# Buzzer.net
KiCad netlist of a schematic drawn in Altium Designer
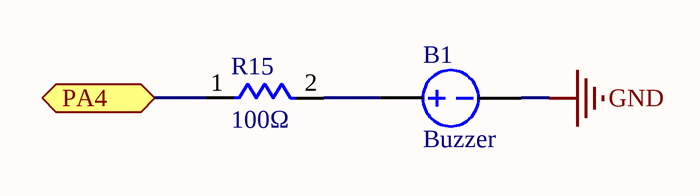
[diagram p0: Buzzer.SchDoc]

(export (version "E")
  (design (tool "Eeschema 10.0.6"))
  (components
    (comp (ref "B1")
      (value "Buzzer")
      (footprint "Buzzer")
      (libsource (lib "Faydali_Yuk_Schlib1") (part "Buzzer"))
    )
    (comp (ref "R15")
      (value "100Ω")
      (footprint "RES - 0603")
      (description "SMD Res")
      (libsource (lib "Faydali_Yuk_Schlib1") (part "Res"))
    )
  )
  (nets
    (net (code "1") (name "/PA4") (class "Default")
      (node (ref "R15") (pin "1") (pinfunction "1_1") (pintype "passive"))
    )
    (net (code "2") (name "GND") (class "Default")
      (node (ref "B1") (pin "2") (pinfunction "2_2") (pintype "passive"))
    )
    (net (code "3") (name "Net-(B1-Pad1)") (class "Default")
      (node (ref "B1") (pin "1") (pinfunction "1_1") (pintype "passive"))
      (node (ref "R15") (pin "2") (pinfunction "2_2") (pintype "passive"))
    )
  )
)
